# TFT-Board.net
KiCad netlist of a schematic drawn in EAGLE
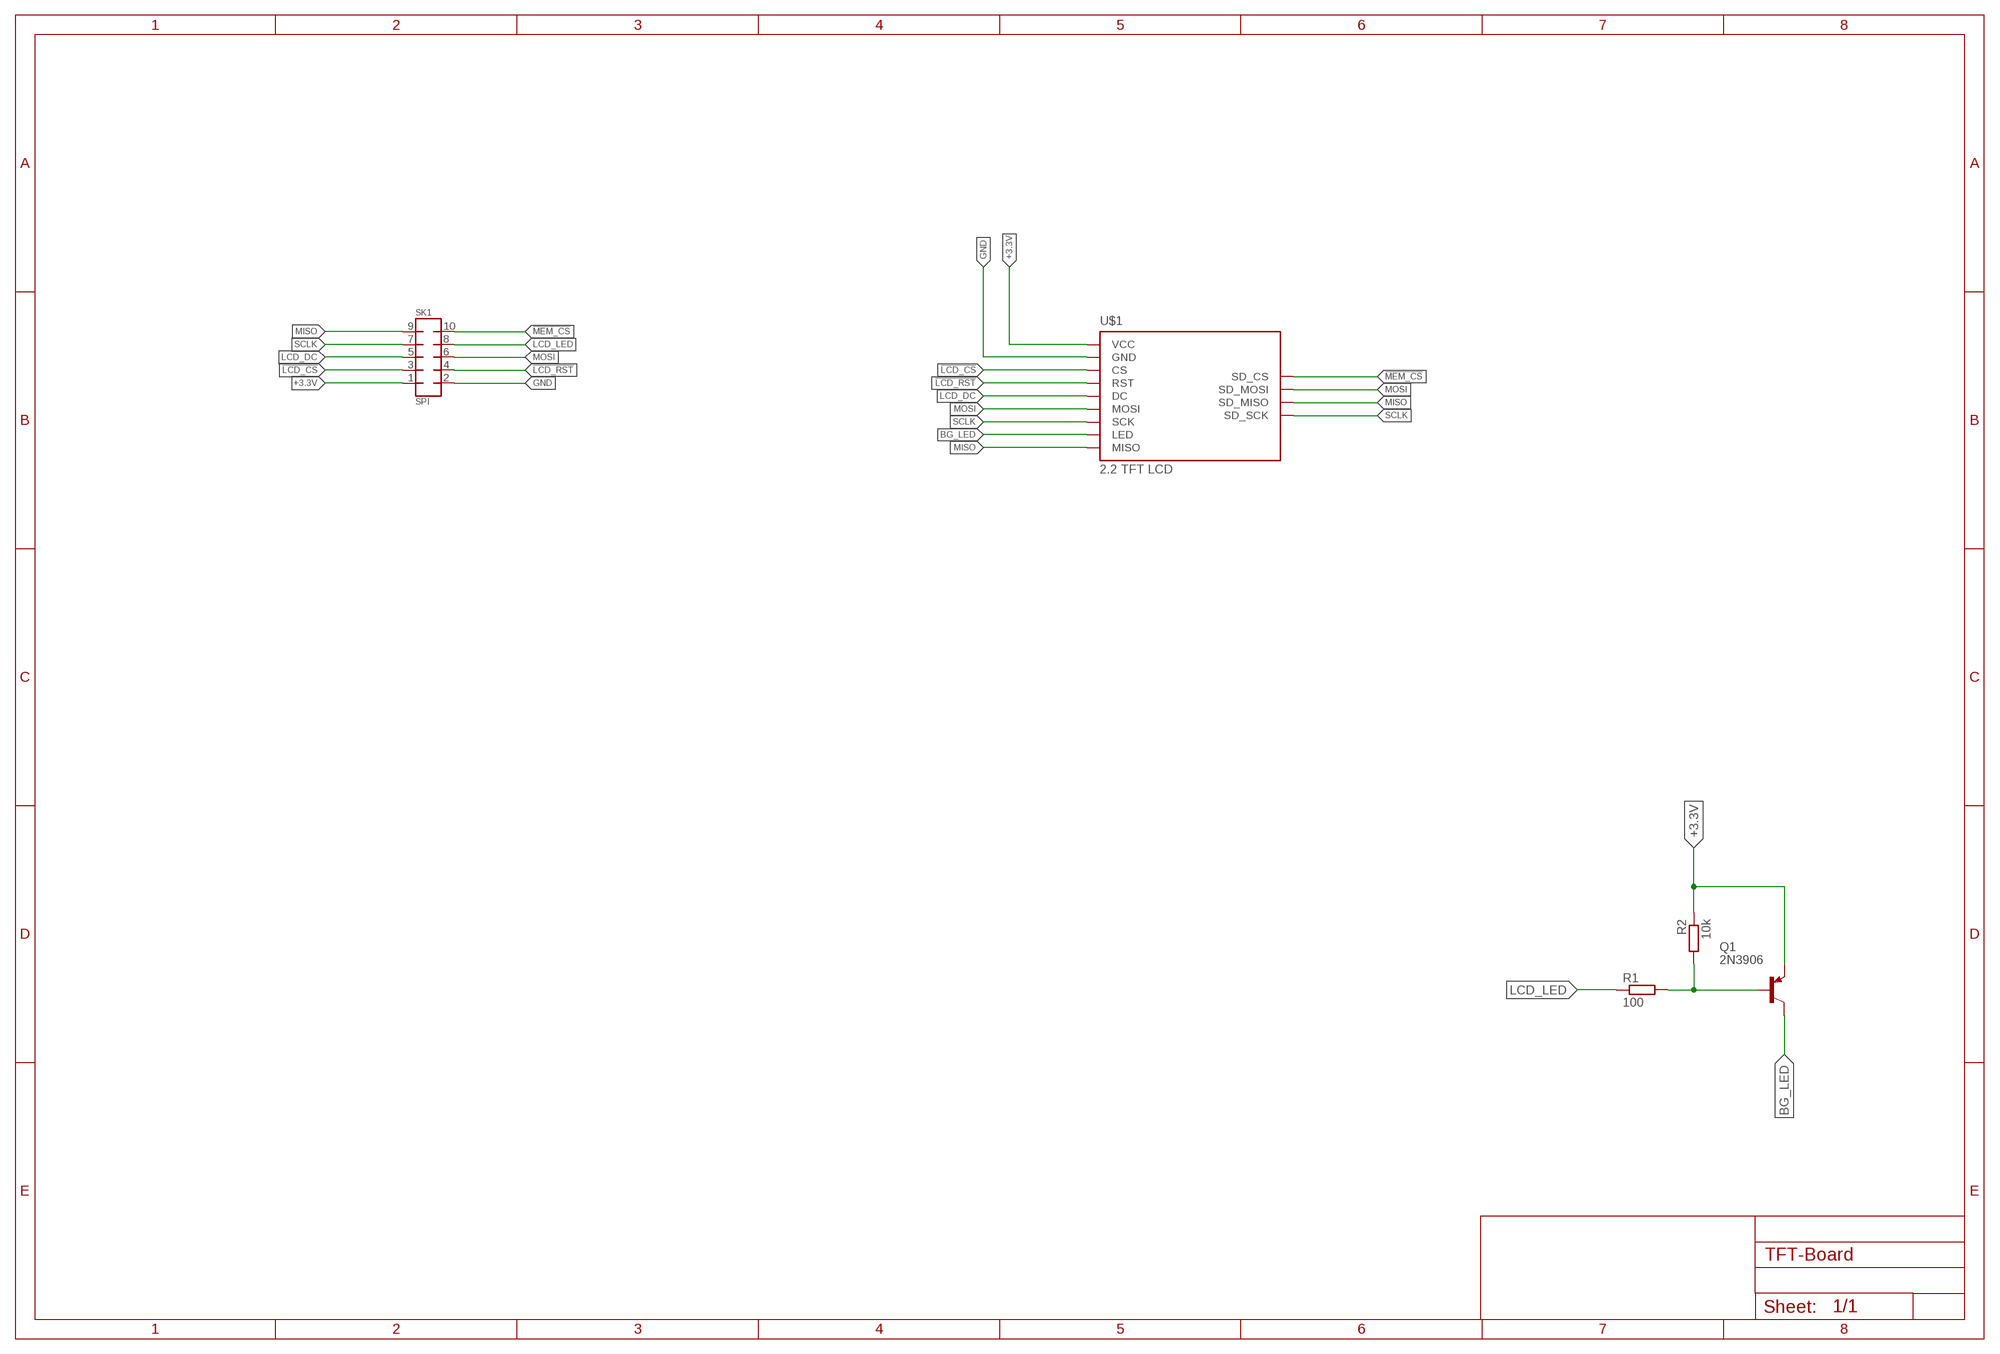
[diagram p0: schematic, sheet 1]

(export (version "E")
  (design (tool "Eeschema 10.0.6"))
  (components
    (comp (ref "Q1")
      (value "2N3906")
      (footprint "eagle-import:TO92")
      (libsource (lib "eagle-import") (part "2N3906"))
    )
    (comp (ref "R1")
      (value "100")
      (footprint "eagle-import:0204_7")
      (libsource (lib "eagle-import") (part "R-EU_0204/7"))
    )
    (comp (ref "R2")
      (value "10k")
      (footprint "eagle-import:0204_7")
      (libsource (lib "eagle-import") (part "R-EU_0204/7"))
    )
    (comp (ref "SK1")
      (value "SPI")
      (footprint "eagle-import:AMP-215079-10")
      (libsource (lib "eagle-import") (part "MMATCH-10-PTH"))
    )
    (comp (ref "U$1")
      (value "2.2_TFT_LCDNEW")
      (footprint "eagle-import:2.2_TFT_LCD_LEDSEE")
      (libsource (lib "eagle-import") (part "2.2_TFT_LCDNEW"))
    )
  )
  (nets
    (net (code "1") (name "+3.3V") (class "Default")
      (node (ref "Q1") (pin "3") (pinfunction "E_3") (pintype "passive"))
      (node (ref "R2") (pin "1") (pinfunction "1_1") (pintype "passive"))
      (node (ref "SK1") (pin "1") (pinfunction "1_1") (pintype "bidirectional"))
      (node (ref "U$1") (pin "P$5_VCC") (pinfunction "VCC_P$5_VCC") (pintype "power_in"))
    )
    (net (code "2") (name "/~{LCD_CS}") (class "Default")
      (node (ref "SK1") (pin "3") (pinfunction "3_3") (pintype "bidirectional"))
      (node (ref "U$1") (pin "P$3_CS") (pinfunction "CS_P$3_CS") (pintype "bidirectional"))
    )
    (net (code "3") (name "/~{LCD_RST}") (class "Default")
      (node (ref "SK1") (pin "4") (pinfunction "4_4") (pintype "bidirectional"))
      (node (ref "U$1") (pin "P$2_RESET") (pinfunction "RST_P$2_RESET") (pintype "bidirectional"))
    )
    (net (code "4") (name "/~{MEM_CS}") (class "Default")
      (node (ref "SK1") (pin "10") (pinfunction "10_10") (pintype "bidirectional"))
      (node (ref "U$1") (pin "P$2_SD_CS") (pinfunction "SD_CS_P$2_SD_CS") (pintype "bidirectional"))
    )
    (net (code "5") (name "BG_LED") (class "Default")
      (node (ref "Q1") (pin "1") (pinfunction "C_1") (pintype "passive"))
      (node (ref "U$1") (pin "P$8_LED") (pinfunction "LED_P$8_LED") (pintype "bidirectional"))
    )
    (net (code "6") (name "GND") (class "Default")
      (node (ref "SK1") (pin "2") (pinfunction "2_2") (pintype "bidirectional"))
      (node (ref "U$1") (pin "P$4_GND") (pinfunction "GND_P$4_GND") (pintype "power_in"))
    )
    (net (code "7") (name "LCD_DC") (class "Default")
      (node (ref "SK1") (pin "5") (pinfunction "5_5") (pintype "bidirectional"))
      (node (ref "U$1") (pin "P$1_DC") (pinfunction "DC_P$1_DC") (pintype "bidirectional"))
    )
    (net (code "8") (name "LCD_LED") (class "Default")
      (node (ref "R1") (pin "1") (pinfunction "1_1") (pintype "passive"))
      (node (ref "SK1") (pin "8") (pinfunction "8_8") (pintype "bidirectional"))
    )
    (net (code "9") (name "MISO") (class "Default")
      (node (ref "SK1") (pin "9") (pinfunction "9_9") (pintype "bidirectional"))
      (node (ref "U$1") (pin "P$3_SD_MISO") (pinfunction "SD_MISO_P$3_SD_MISO") (pintype "bidirectional"))
      (node (ref "U$1") (pin "P$9_MISO") (pinfunction "MISO_P$9_MISO") (pintype "bidirectional"))
    )
    (net (code "10") (name "MOSI") (class "Default")
      (node (ref "SK1") (pin "6") (pinfunction "6_6") (pintype "bidirectional"))
      (node (ref "U$1") (pin "P$1_SD_MOSI") (pinfunction "SD_MOSI_P$1_SD_MOSI") (pintype "bidirectional"))
      (node (ref "U$1") (pin "P$6_MOSI") (pinfunction "MOSI_P$6_MOSI") (pintype "bidirectional"))
    )
    (net (code "11") (name "Net-(Q1-B)") (class "Default")
      (node (ref "Q1") (pin "2") (pinfunction "B_2") (pintype "passive"))
      (node (ref "R1") (pin "2") (pinfunction "2_2") (pintype "passive"))
      (node (ref "R2") (pin "2") (pinfunction "2_2") (pintype "passive"))
    )
    (net (code "12") (name "SCLK") (class "Default")
      (node (ref "SK1") (pin "7") (pinfunction "7_7") (pintype "bidirectional"))
      (node (ref "U$1") (pin "P$4_SD_SCK") (pinfunction "SD_SCK_P$4_SD_SCK") (pintype "bidirectional"))
      (node (ref "U$1") (pin "P$7_SCK") (pinfunction "SCK_P$7_SCK") (pintype "bidirectional"))
    )
  )
)
